# Qwiic_Multi_Distance_Sensor_-_VL53L3CX.net
KiCad netlist of a schematic drawn in EAGLE
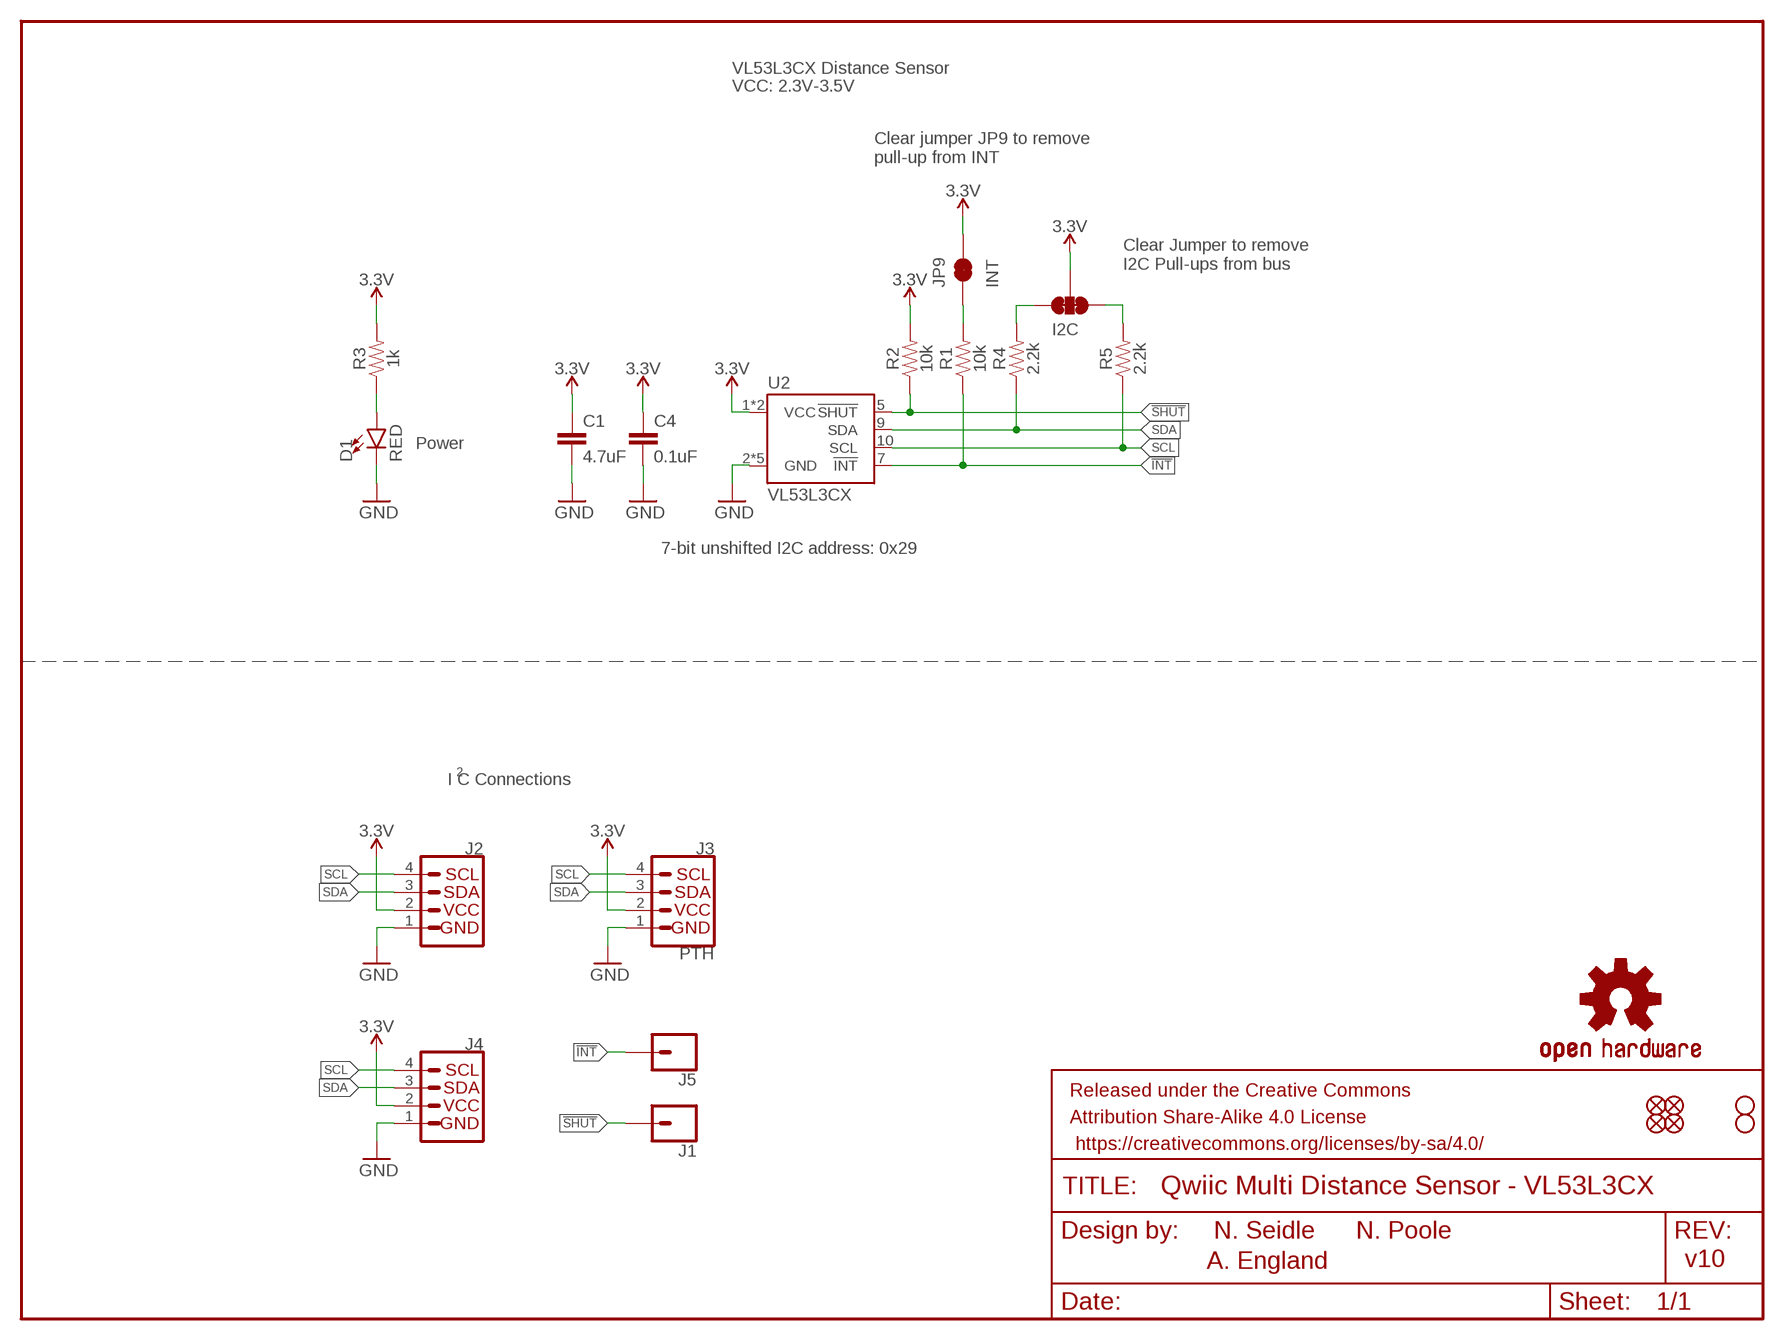
[diagram p0: schematic, sheet 1]

(export (version "E")
  (design (tool "Eeschema 10.0.6"))
  (components
    (comp (ref "C1")
      (value "4.7uF")
      (footprint "eagle-import:0603")
      (libsource (lib "eagle-import") (part "4.7UF0603"))
    )
    (comp (ref "C4")
      (value "0.1uF")
      (footprint "eagle-import:0603")
      (libsource (lib "eagle-import") (part "0.1UF-0603-25V-(+80/-20%)"))
    )
    (comp (ref "D1")
      (value "RED")
      (footprint "eagle-import:LED-0603")
      (libsource (lib "eagle-import") (part "LED-RED0603"))
    )
    (comp (ref "FRAME1")
      (value "FRAME-LETTERNO_PACKAGE")
      (footprint "eagle-import:DUMMY")
      (fields (field (name "DESIGNER") "Nobody"))
      (libsource (lib "eagle-import") (part "FRAME-LETTERNO_PACKAGE"))
    )
    (comp (ref "I2C")
      (value "JUMPER-SMT_3_2-NC_TRACE_SILK")
      (footprint "eagle-import:SMT-JUMPER_3_2-NC_TRACE_SILK")
      (libsource (lib "eagle-import") (part "JUMPER-SMT_3_2-NC_TRACE_SILK"))
    )
    (comp (ref "J1")
      (value "CONN_01PTH_NO_SILK_YES_STOP")
      (footprint "eagle-import:1X01_NO_SILK")
      (libsource (lib "eagle-import") (part "CONN_01PTH_NO_SILK_YES_STOP"))
    )
    (comp (ref "J2")
      (value "QWIIC_CONNECTORJS-1MM")
      (footprint "eagle-import:1X04_1MM_RA")
      (libsource (lib "eagle-import") (part "QWIIC_CONNECTORJS-1MM"))
    )
    (comp (ref "J3")
      (value "PTH")
      (footprint "eagle-import:1X04_NO_SILK")
      (libsource (lib "eagle-import") (part "I2C_STANDARD_NO_SILK"))
    )
    (comp (ref "J4")
      (value "QWIIC_CONNECTORJS-1MM")
      (footprint "eagle-import:1X04_1MM_RA")
      (libsource (lib "eagle-import") (part "QWIIC_CONNECTORJS-1MM"))
    )
    (comp (ref "J5")
      (value "CONN_01PTH_NO_SILK_YES_STOP")
      (footprint "eagle-import:1X01_NO_SILK")
      (libsource (lib "eagle-import") (part "CONN_01PTH_NO_SILK_YES_STOP"))
    )
    (comp (ref "JP1")
      (value "FIDUCIALUFIDUCIAL")
      (footprint "eagle-import:MICRO-FIDUCIAL")
      (libsource (lib "eagle-import") (part "FIDUCIALUFIDUCIAL"))
    )
    (comp (ref "JP2")
      (value "FIDUCIALUFIDUCIAL")
      (footprint "eagle-import:MICRO-FIDUCIAL")
      (libsource (lib "eagle-import") (part "FIDUCIALUFIDUCIAL"))
    )
    (comp (ref "JP3")
      (value "STAND-OFF")
      (footprint "eagle-import:STAND-OFF")
      (libsource (lib "eagle-import") (part "STAND-OFF"))
    )
    (comp (ref "JP4")
      (value "STAND-OFF")
      (footprint "eagle-import:STAND-OFF")
      (libsource (lib "eagle-import") (part "STAND-OFF"))
    )
    (comp (ref "JP5")
      (value "FIDUCIALUFIDUCIAL")
      (footprint "eagle-import:MICRO-FIDUCIAL")
      (libsource (lib "eagle-import") (part "FIDUCIALUFIDUCIAL"))
    )
    (comp (ref "JP6")
      (value "FIDUCIALUFIDUCIAL")
      (footprint "eagle-import:MICRO-FIDUCIAL")
      (libsource (lib "eagle-import") (part "FIDUCIALUFIDUCIAL"))
    )
    (comp (ref "JP9")
      (value "INT")
      (footprint "eagle-import:PAD-JUMPER-2-NC_BY_TRACE_YES_SILK")
      (libsource (lib "eagle-import") (part "JUMPER-PAD-2-NC_BY_TRACE"))
    )
    (comp (ref "LOGO1")
      (value "OSHW-LOGOMINI")
      (footprint "eagle-import:OSHW-LOGO-MINI")
      (libsource (lib "eagle-import") (part "OSHW-LOGOMINI"))
    )
    (comp (ref "R1")
      (value "10k")
      (footprint "eagle-import:0603")
      (libsource (lib "eagle-import") (part "10KOHM-0603-1/10W-1%"))
    )
    (comp (ref "R2")
      (value "10k")
      (footprint "eagle-import:0603")
      (libsource (lib "eagle-import") (part "10KOHM-0603-1/10W-1%"))
    )
    (comp (ref "R3")
      (value "1k")
      (footprint "eagle-import:0603")
      (libsource (lib "eagle-import") (part "1KOHM-0603-1/10W-1%"))
    )
    (comp (ref "R4")
      (value "2.2k")
      (footprint "eagle-import:0603")
      (libsource (lib "eagle-import") (part "2.2KOHM-0603-1/10W-1%"))
    )
    (comp (ref "R5")
      (value "2.2k")
      (footprint "eagle-import:0603")
      (libsource (lib "eagle-import") (part "2.2KOHM-0603-1/10W-1%"))
    )
    (comp (ref "U2")
      (value "VL53L3CX")
      (footprint "eagle-import:VL53L1X")
      (libsource (lib "eagle-import") (part "VL53L1XSMD"))
    )
  )
  (nets
    (net (code "1") (name "/~{INT}") (class "Default")
      (node (ref "J5") (pin "1") (pinfunction "1_1") (pintype "passive"))
      (node (ref "R1") (pin "1") (pinfunction "1_1") (pintype "passive"))
      (node (ref "U2") (pin "7") (pinfunction "~{INT}_7") (pintype "bidirectional"))
    )
    (net (code "2") (name "/~{SHUT}") (class "Default")
      (node (ref "J1") (pin "1") (pinfunction "1_1") (pintype "passive"))
      (node (ref "R2") (pin "1") (pinfunction "1_1") (pintype "passive"))
      (node (ref "U2") (pin "5") (pinfunction "~{SHUT}_5") (pintype "bidirectional"))
    )
    (net (code "3") (name "3.3V") (class "Default")
      (node (ref "C1") (pin "1") (pinfunction "1_1") (pintype "passive"))
      (node (ref "C4") (pin "1") (pinfunction "1_1") (pintype "passive"))
      (node (ref "I2C") (pin "2") (pinfunction "2_2") (pintype "passive"))
      (node (ref "J2") (pin "2") (pinfunction "2_2") (pintype "power_in"))
      (node (ref "J3") (pin "2") (pinfunction "VCC_2") (pintype "power_in"))
      (node (ref "J4") (pin "2") (pinfunction "2_2") (pintype "power_in"))
      (node (ref "JP9") (pin "2") (pinfunction "2_2") (pintype "passive"))
      (node (ref "R2") (pin "2") (pinfunction "2_2") (pintype "passive"))
      (node (ref "R3") (pin "2") (pinfunction "2_2") (pintype "passive"))
      (node (ref "U2") (pin "1") (pinfunction "VCC_1") (pintype "bidirectional"))
      (node (ref "U2") (pin "11") (pinfunction "VCC_11") (pintype "bidirectional"))
    )
    (net (code "4") (name "GND") (class "Default")
      (node (ref "C1") (pin "2") (pinfunction "2_2") (pintype "passive"))
      (node (ref "C4") (pin "2") (pinfunction "2_2") (pintype "passive"))
      (node (ref "D1") (pin "C") (pinfunction "C_C") (pintype "passive"))
      (node (ref "J2") (pin "1") (pinfunction "1_1") (pintype "power_in"))
      (node (ref "J3") (pin "1") (pinfunction "GND_1") (pintype "power_in"))
      (node (ref "J4") (pin "1") (pinfunction "1_1") (pintype "power_in"))
      (node (ref "U2") (pin "12") (pinfunction "GND_12") (pintype "bidirectional"))
      (node (ref "U2") (pin "2") (pinfunction "GND_2") (pintype "bidirectional"))
      (node (ref "U2") (pin "3") (pinfunction "GND_3") (pintype "bidirectional"))
      (node (ref "U2") (pin "4") (pinfunction "GND_4") (pintype "bidirectional"))
      (node (ref "U2") (pin "6") (pinfunction "GND_6") (pintype "bidirectional"))
    )
    (net (code "5") (name "Net-(D1-PadA)") (class "Default")
      (node (ref "D1") (pin "A") (pinfunction "A_A") (pintype "passive"))
      (node (ref "R3") (pin "1") (pinfunction "1_1") (pintype "passive"))
    )
    (net (code "6") (name "Net-(I2C-Pad1)") (class "Default")
      (node (ref "I2C") (pin "1") (pinfunction "1_1") (pintype "passive"))
      (node (ref "R5") (pin "2") (pinfunction "2_2") (pintype "passive"))
    )
    (net (code "7") (name "Net-(I2C-Pad3)") (class "Default")
      (node (ref "I2C") (pin "3") (pinfunction "3_3") (pintype "passive"))
      (node (ref "R4") (pin "2") (pinfunction "2_2") (pintype "passive"))
    )
    (net (code "8") (name "Net-(JP9-Pad1)") (class "Default")
      (node (ref "JP9") (pin "1") (pinfunction "1_1") (pintype "passive"))
      (node (ref "R1") (pin "2") (pinfunction "2_2") (pintype "passive"))
    )
    (net (code "9") (name "SCL") (class "Default")
      (node (ref "J2") (pin "4") (pinfunction "4_4") (pintype "passive"))
      (node (ref "J3") (pin "4") (pinfunction "SCL_4") (pintype "passive"))
      (node (ref "J4") (pin "4") (pinfunction "4_4") (pintype "passive"))
      (node (ref "R5") (pin "1") (pinfunction "1_1") (pintype "passive"))
      (node (ref "U2") (pin "10") (pinfunction "SCL_10") (pintype "bidirectional"))
    )
    (net (code "10") (name "SDA") (class "Default")
      (node (ref "J2") (pin "3") (pinfunction "3_3") (pintype "passive"))
      (node (ref "J3") (pin "3") (pinfunction "SDA_3") (pintype "passive"))
      (node (ref "J4") (pin "3") (pinfunction "3_3") (pintype "passive"))
      (node (ref "R4") (pin "1") (pinfunction "1_1") (pintype "passive"))
      (node (ref "U2") (pin "9") (pinfunction "SDA_9") (pintype "bidirectional"))
    )
  )
)
